# STM.net
KiCad netlist of a schematic drawn in Altium Designer
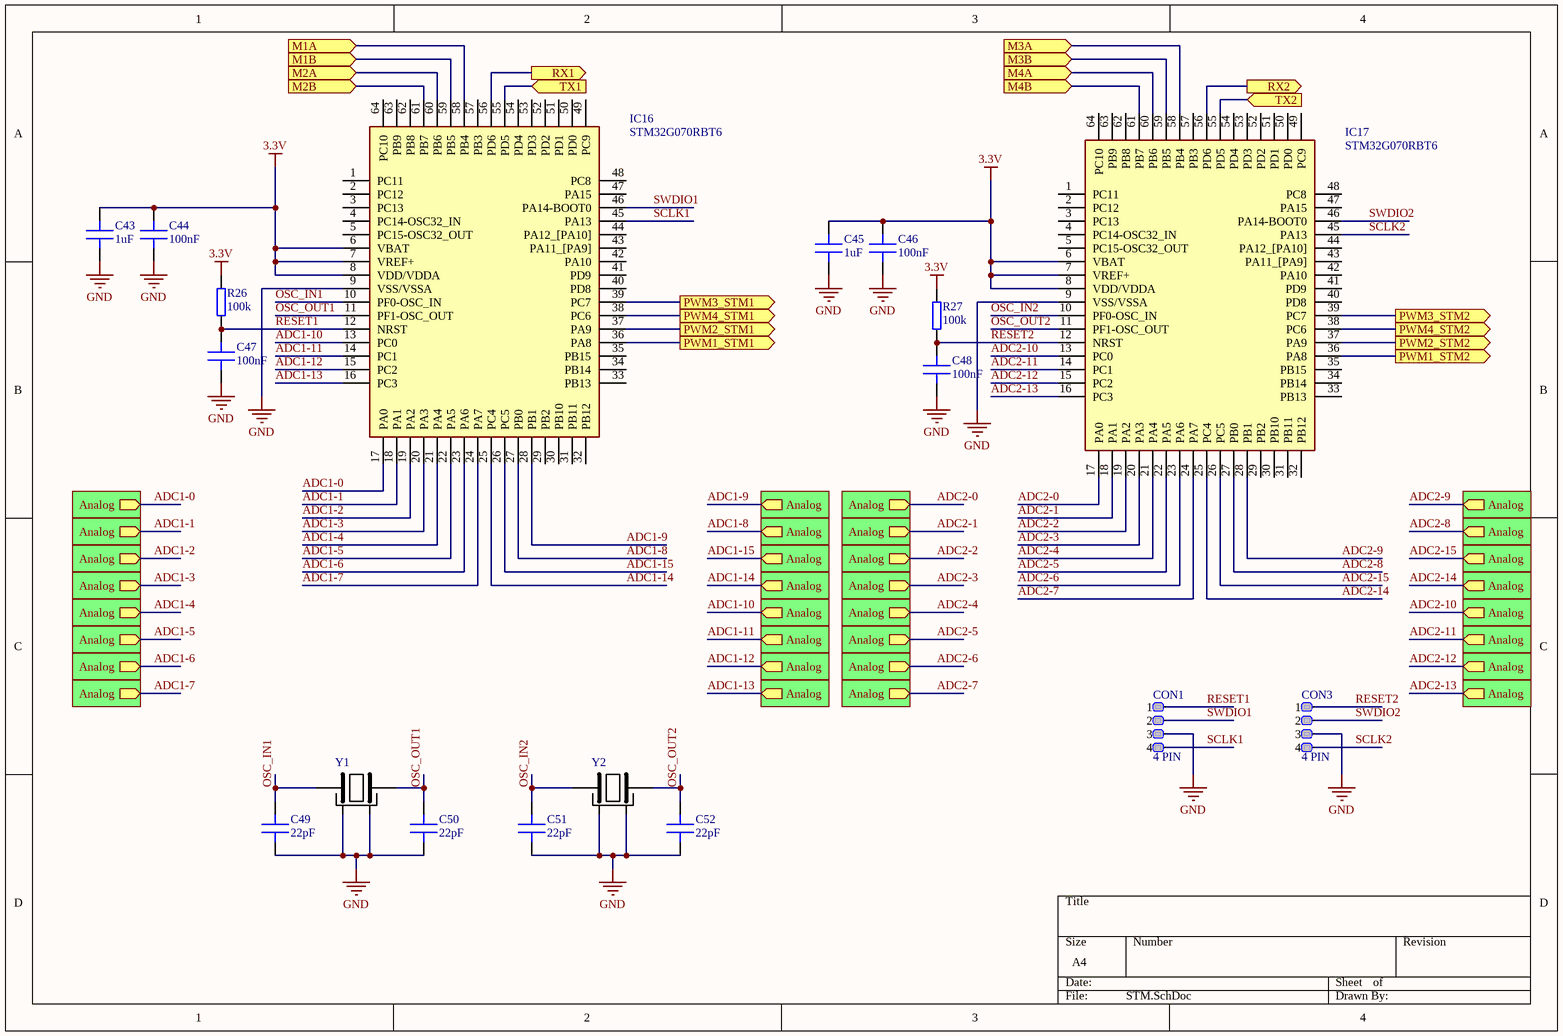
[diagram p0: STM.SchDoc]

(export (version "E")
  (design (tool "Eeschema 10.0.6"))
  (components
    (comp (ref "C43")
      (value "1uF")
      (footprint "C 0402")
      (description "MLCC Capacitor")
      (libsource (lib "Components") (part "Capacitor"))
    )
    (comp (ref "C44")
      (value "100nF")
      (footprint "C 0402")
      (description "MLCC Capacitor")
      (libsource (lib "Components") (part "Capacitor"))
    )
    (comp (ref "C45")
      (value "1uF")
      (footprint "C 0402")
      (description "MLCC Capacitor")
      (libsource (lib "Components") (part "Capacitor"))
    )
    (comp (ref "C46")
      (value "100nF")
      (footprint "C 0402")
      (description "MLCC Capacitor")
      (libsource (lib "Components") (part "Capacitor"))
    )
    (comp (ref "C47")
      (value "100nF")
      (footprint "C 0402")
      (description "MLCC Capacitor")
      (libsource (lib "Components") (part "Capacitor"))
    )
    (comp (ref "C48")
      (value "100nF")
      (footprint "C 0402")
      (description "MLCC Capacitor")
      (libsource (lib "Components") (part "Capacitor"))
    )
    (comp (ref "C49")
      (value "22pF")
      (footprint "C 0402")
      (description "MLCC Capacitor")
      (libsource (lib "Components") (part "Capacitor"))
    )
    (comp (ref "C50")
      (value "22pF")
      (footprint "C 0402")
      (description "MLCC Capacitor")
      (libsource (lib "Components") (part "Capacitor"))
    )
    (comp (ref "C51")
      (value "22pF")
      (footprint "C 0402")
      (description "MLCC Capacitor")
      (libsource (lib "Components") (part "Capacitor"))
    )
    (comp (ref "C52")
      (value "22pF")
      (footprint "C 0402")
      (description "MLCC Capacitor")
      (libsource (lib "Components") (part "Capacitor"))
    )
    (comp (ref "CON1")
      (value "4 PIN")
      (footprint "BM04B-SRSS-TB")
      (libsource (lib "Connectors") (part "4 PIN"))
    )
    (comp (ref "CON3")
      (value "4 PIN")
      (footprint "BM04B-SRSS-TB")
      (libsource (lib "Connectors") (part "4 PIN"))
    )
    (comp (ref "IC16")
      (value "STM32G070RBT6")
      (footprint "SamacSys:QFP50P1200X1200X160-64N")
      (description "Integrated Circuit")
      (fields (field (name "MOUSER PART NUMBER") "511-STM32G070RBT6"))
      (libsource (lib "*") (part "STM32G070RBT6"))
    )
    (comp (ref "IC17")
      (value "STM32G070RBT6")
      (footprint "SamacSys:QFP50P1200X1200X160-64N")
      (description "Integrated Circuit")
      (fields (field (name "MOUSER PART NUMBER") "511-STM32G070RBT6"))
      (libsource (lib "*") (part "STM32G070RBT6"))
    )
    (comp (ref "R26")
      (value "100k")
      (footprint "R 0402")
      (description "General pourpouse resistor")
      (libsource (lib "Components") (part "Resistor"))
    )
    (comp (ref "R27")
      (value "100k")
      (footprint "R 0402")
      (description "General pourpouse resistor")
      (libsource (lib "Components") (part "Resistor"))
    )
    (comp (ref "Y1")
      (value "MCSJK-7U-16.00-12-30-80-B-30")
      (footprint "MCSJK7U1600123080B30")
      (description "Crystal or Oscillator")
      (libsource (lib "SamaSycLibraies") (part "MCSJK-7U-16.00-12-30-80-B-30"))
    )
    (comp (ref "Y2")
      (value "MCSJK-7U-16.00-12-30-80-B-30")
      (footprint "MCSJK7U1600123080B30")
      (description "Crystal or Oscillator")
      (libsource (lib "SamaSycLibraies") (part "MCSJK-7U-16.00-12-30-80-B-30"))
    )
  )
  (nets
    (net (code "1") (name "/ADC1-0") (class "Default")
      (node (ref "IC16") (pin "17") (pinfunction "PA0_17") (pintype "passive"))
    )
    (net (code "2") (name "/ADC1-1") (class "Default")
      (node (ref "IC16") (pin "18") (pinfunction "PA1_18") (pintype "passive"))
    )
    (net (code "3") (name "/ADC1-2") (class "Default")
      (node (ref "IC16") (pin "19") (pinfunction "PA2_19") (pintype "passive"))
    )
    (net (code "4") (name "/ADC1-3") (class "Default")
      (node (ref "IC16") (pin "20") (pinfunction "PA3_20") (pintype "passive"))
    )
    (net (code "5") (name "/ADC1-4") (class "Default")
      (node (ref "IC16") (pin "21") (pinfunction "PA4_21") (pintype "passive"))
    )
    (net (code "6") (name "/ADC1-5") (class "Default")
      (node (ref "IC16") (pin "22") (pinfunction "PA5_22") (pintype "passive"))
    )
    (net (code "7") (name "/ADC1-6") (class "Default")
      (node (ref "IC16") (pin "23") (pinfunction "PA6_23") (pintype "passive"))
    )
    (net (code "8") (name "/ADC1-7") (class "Default")
      (node (ref "IC16") (pin "24") (pinfunction "PA7_24") (pintype "passive"))
    )
    (net (code "9") (name "/ADC1-8") (class "Default")
      (node (ref "IC16") (pin "27") (pinfunction "PB0_27") (pintype "passive"))
    )
    (net (code "10") (name "/ADC1-9") (class "Default")
      (node (ref "IC16") (pin "28") (pinfunction "PB1_28") (pintype "passive"))
    )
    (net (code "11") (name "/ADC1-10") (class "Default")
      (node (ref "IC16") (pin "13") (pinfunction "PC0_13") (pintype "passive"))
    )
    (net (code "12") (name "/ADC1-11") (class "Default")
      (node (ref "IC16") (pin "14") (pinfunction "PC1_14") (pintype "passive"))
    )
    (net (code "13") (name "/ADC1-12") (class "Default")
      (node (ref "IC16") (pin "15") (pinfunction "PC2_15") (pintype "passive"))
    )
    (net (code "14") (name "/ADC1-13") (class "Default")
      (node (ref "IC16") (pin "16") (pinfunction "PC3_16") (pintype "passive"))
    )
    (net (code "15") (name "/ADC1-14") (class "Default")
      (node (ref "IC16") (pin "25") (pinfunction "PC4_25") (pintype "passive"))
    )
    (net (code "16") (name "/ADC1-15") (class "Default")
      (node (ref "IC16") (pin "26") (pinfunction "PC5_26") (pintype "passive"))
    )
    (net (code "17") (name "/ADC2-0") (class "Default")
      (node (ref "IC17") (pin "17") (pinfunction "PA0_17") (pintype "passive"))
    )
    (net (code "18") (name "/ADC2-1") (class "Default")
      (node (ref "IC17") (pin "18") (pinfunction "PA1_18") (pintype "passive"))
    )
    (net (code "19") (name "/ADC2-2") (class "Default")
      (node (ref "IC17") (pin "19") (pinfunction "PA2_19") (pintype "passive"))
    )
    (net (code "20") (name "/ADC2-3") (class "Default")
      (node (ref "IC17") (pin "20") (pinfunction "PA3_20") (pintype "passive"))
    )
    (net (code "21") (name "/ADC2-4") (class "Default")
      (node (ref "IC17") (pin "21") (pinfunction "PA4_21") (pintype "passive"))
    )
    (net (code "22") (name "/ADC2-5") (class "Default")
      (node (ref "IC17") (pin "22") (pinfunction "PA5_22") (pintype "passive"))
    )
    (net (code "23") (name "/ADC2-6") (class "Default")
      (node (ref "IC17") (pin "23") (pinfunction "PA6_23") (pintype "passive"))
    )
    (net (code "24") (name "/ADC2-7") (class "Default")
      (node (ref "IC17") (pin "24") (pinfunction "PA7_24") (pintype "passive"))
    )
    (net (code "25") (name "/ADC2-8") (class "Default")
      (node (ref "IC17") (pin "27") (pinfunction "PB0_27") (pintype "passive"))
    )
    (net (code "26") (name "/ADC2-9") (class "Default")
      (node (ref "IC17") (pin "28") (pinfunction "PB1_28") (pintype "passive"))
    )
    (net (code "27") (name "/ADC2-10") (class "Default")
      (node (ref "IC17") (pin "13") (pinfunction "PC0_13") (pintype "passive"))
    )
    (net (code "28") (name "/ADC2-11") (class "Default")
      (node (ref "IC17") (pin "14") (pinfunction "PC1_14") (pintype "passive"))
    )
    (net (code "29") (name "/ADC2-12") (class "Default")
      (node (ref "IC17") (pin "15") (pinfunction "PC2_15") (pintype "passive"))
    )
    (net (code "30") (name "/ADC2-13") (class "Default")
      (node (ref "IC17") (pin "16") (pinfunction "PC3_16") (pintype "passive"))
    )
    (net (code "31") (name "/ADC2-14") (class "Default")
      (node (ref "IC17") (pin "25") (pinfunction "PC4_25") (pintype "passive"))
    )
    (net (code "32") (name "/ADC2-15") (class "Default")
      (node (ref "IC17") (pin "26") (pinfunction "PC5_26") (pintype "passive"))
    )
    (net (code "33") (name "/M1A") (class "Default")
      (node (ref "IC16") (pin "58") (pinfunction "PB4_58") (pintype "passive"))
    )
    (net (code "34") (name "/M1B") (class "Default")
      (node (ref "IC16") (pin "59") (pinfunction "PB5_59") (pintype "passive"))
    )
    (net (code "35") (name "/M2A") (class "Default")
      (node (ref "IC16") (pin "60") (pinfunction "PB6_60") (pintype "passive"))
    )
    (net (code "36") (name "/M2B") (class "Default")
      (node (ref "IC16") (pin "61") (pinfunction "PB7_61") (pintype "passive"))
    )
    (net (code "37") (name "/M3A") (class "Default")
      (node (ref "IC17") (pin "58") (pinfunction "PB4_58") (pintype "passive"))
    )
    (net (code "38") (name "/M3B") (class "Default")
      (node (ref "IC17") (pin "59") (pinfunction "PB5_59") (pintype "passive"))
    )
    (net (code "39") (name "/M4A") (class "Default")
      (node (ref "IC17") (pin "60") (pinfunction "PB6_60") (pintype "passive"))
    )
    (net (code "40") (name "/M4B") (class "Default")
      (node (ref "IC17") (pin "61") (pinfunction "PB7_61") (pintype "passive"))
    )
    (net (code "41") (name "/OSC_IN1") (class "Default")
      (node (ref "C49") (pin "1") (pinfunction "1_1") (pintype "passive"))
      (node (ref "IC16") (pin "10") (pinfunction "PF0-OSC_IN_10") (pintype "passive"))
      (node (ref "Y1") (pin "1") (pinfunction "CRYSTAL_1_1") (pintype "passive"))
    )
    (net (code "42") (name "/OSC_IN2") (class "Default")
      (node (ref "C51") (pin "1") (pinfunction "1_1") (pintype "passive"))
      (node (ref "IC17") (pin "10") (pinfunction "PF0-OSC_IN_10") (pintype "passive"))
      (node (ref "Y2") (pin "1") (pinfunction "CRYSTAL_1_1") (pintype "passive"))
    )
    (net (code "43") (name "/OSC_OUT1") (class "Default")
      (node (ref "C50") (pin "1") (pinfunction "1_1") (pintype "passive"))
      (node (ref "IC16") (pin "11") (pinfunction "PF1-OSC_OUT_11") (pintype "passive"))
      (node (ref "Y1") (pin "3") (pinfunction "CRYSTAL_2_3") (pintype "passive"))
    )
    (net (code "44") (name "/OSC_OUT2") (class "Default")
      (node (ref "C52") (pin "1") (pinfunction "1_1") (pintype "passive"))
      (node (ref "IC17") (pin "11") (pinfunction "PF1-OSC_OUT_11") (pintype "passive"))
      (node (ref "Y2") (pin "3") (pinfunction "CRYSTAL_2_3") (pintype "passive"))
    )
    (net (code "45") (name "/PWM1_STM1") (class "Default")
      (node (ref "IC16") (pin "36") (pinfunction "PA8_36") (pintype "passive"))
    )
    (net (code "46") (name "/PWM1_STM2") (class "Default")
      (node (ref "IC17") (pin "36") (pinfunction "PA8_36") (pintype "passive"))
    )
    (net (code "47") (name "/PWM2_STM1") (class "Default")
      (node (ref "IC16") (pin "37") (pinfunction "PA9_37") (pintype "passive"))
    )
    (net (code "48") (name "/PWM2_STM2") (class "Default")
      (node (ref "IC17") (pin "37") (pinfunction "PA9_37") (pintype "passive"))
    )
    (net (code "49") (name "/PWM3_STM1") (class "Default")
      (node (ref "IC16") (pin "39") (pinfunction "PC7_39") (pintype "passive"))
    )
    (net (code "50") (name "/PWM3_STM2") (class "Default")
      (node (ref "IC17") (pin "39") (pinfunction "PC7_39") (pintype "passive"))
    )
    (net (code "51") (name "/PWM4_STM1") (class "Default")
      (node (ref "IC16") (pin "38") (pinfunction "PC6_38") (pintype "passive"))
    )
    (net (code "52") (name "/PWM4_STM2") (class "Default")
      (node (ref "IC17") (pin "38") (pinfunction "PC6_38") (pintype "passive"))
    )
    (net (code "53") (name "/RESET1") (class "Default")
      (node (ref "C47") (pin "1") (pinfunction "1_1") (pintype "passive"))
      (node (ref "CON1") (pin "1") (pinfunction "1_1") (pintype "passive"))
      (node (ref "IC16") (pin "12") (pinfunction "NRST_12") (pintype "passive"))
      (node (ref "R26") (pin "1") (pinfunction "1_1") (pintype "passive"))
    )
    (net (code "54") (name "/RESET2") (class "Default")
      (node (ref "C48") (pin "1") (pinfunction "1_1") (pintype "passive"))
      (node (ref "CON3") (pin "1") (pinfunction "1_1") (pintype "passive"))
      (node (ref "IC17") (pin "12") (pinfunction "NRST_12") (pintype "passive"))
      (node (ref "R27") (pin "1") (pinfunction "1_1") (pintype "passive"))
    )
    (net (code "55") (name "/RX1") (class "Default")
      (node (ref "IC16") (pin "56") (pinfunction "PD6_56") (pintype "passive"))
    )
    (net (code "56") (name "/RX2") (class "Default")
      (node (ref "IC17") (pin "56") (pinfunction "PD6_56") (pintype "passive"))
    )
    (net (code "57") (name "/SCLK1") (class "Default")
      (node (ref "CON1") (pin "4") (pinfunction "4_4") (pintype "passive"))
      (node (ref "IC16") (pin "45") (pinfunction "PA13_45") (pintype "passive"))
    )
    (net (code "58") (name "/SCLK2") (class "Default")
      (node (ref "CON3") (pin "4") (pinfunction "4_4") (pintype "passive"))
      (node (ref "IC17") (pin "45") (pinfunction "PA13_45") (pintype "passive"))
    )
    (net (code "59") (name "/SWDIO1") (class "Default")
      (node (ref "CON1") (pin "2") (pinfunction "2_2") (pintype "passive"))
      (node (ref "IC16") (pin "46") (pinfunction "PA14-BOOT0_46") (pintype "passive"))
    )
    (net (code "60") (name "/SWDIO2") (class "Default")
      (node (ref "CON3") (pin "2") (pinfunction "2_2") (pintype "passive"))
      (node (ref "IC17") (pin "46") (pinfunction "PA14-BOOT0_46") (pintype "passive"))
    )
    (net (code "61") (name "/TX1") (class "Default")
      (node (ref "IC16") (pin "55") (pinfunction "PD5_55") (pintype "passive"))
    )
    (net (code "62") (name "/TX2") (class "Default")
      (node (ref "IC17") (pin "55") (pinfunction "PD5_55") (pintype "passive"))
    )
    (net (code "63") (name "3.3V") (class "Default")
      (node (ref "C43") (pin "1") (pinfunction "1_1") (pintype "passive"))
      (node (ref "C44") (pin "1") (pinfunction "1_1") (pintype "passive"))
      (node (ref "C45") (pin "1") (pinfunction "1_1") (pintype "passive"))
      (node (ref "C46") (pin "1") (pinfunction "1_1") (pintype "passive"))
      (node (ref "IC16") (pin "6") (pinfunction "VBAT_6") (pintype "passive"))
      (node (ref "IC16") (pin "7") (pinfunction "VREF+_7") (pintype "passive"))
      (node (ref "IC16") (pin "8") (pinfunction "VDD/VDDA_8") (pintype "passive"))
      (node (ref "IC17") (pin "6") (pinfunction "VBAT_6") (pintype "passive"))
      (node (ref "IC17") (pin "7") (pinfunction "VREF+_7") (pintype "passive"))
      (node (ref "IC17") (pin "8") (pinfunction "VDD/VDDA_8") (pintype "passive"))
      (node (ref "R26") (pin "2") (pinfunction "2_2") (pintype "passive"))
      (node (ref "R27") (pin "2") (pinfunction "2_2") (pintype "passive"))
    )
    (net (code "64") (name "GND") (class "Default")
      (node (ref "C43") (pin "2") (pinfunction "2_2") (pintype "passive"))
      (node (ref "C44") (pin "2") (pinfunction "2_2") (pintype "passive"))
      (node (ref "C45") (pin "2") (pinfunction "2_2") (pintype "passive"))
      (node (ref "C46") (pin "2") (pinfunction "2_2") (pintype "passive"))
      (node (ref "C47") (pin "2") (pinfunction "2_2") (pintype "passive"))
      (node (ref "C48") (pin "2") (pinfunction "2_2") (pintype "passive"))
      (node (ref "C49") (pin "2") (pinfunction "2_2") (pintype "passive"))
      (node (ref "C50") (pin "2") (pinfunction "2_2") (pintype "passive"))
      (node (ref "C51") (pin "2") (pinfunction "2_2") (pintype "passive"))
      (node (ref "C52") (pin "2") (pinfunction "2_2") (pintype "passive"))
      (node (ref "CON1") (pin "3") (pinfunction "3_3") (pintype "passive"))
      (node (ref "CON3") (pin "3") (pinfunction "3_3") (pintype "passive"))
      (node (ref "IC16") (pin "9") (pinfunction "VSS/VSSA_9") (pintype "passive"))
      (node (ref "IC17") (pin "9") (pinfunction "VSS/VSSA_9") (pintype "passive"))
      (node (ref "Y1") (pin "2") (pinfunction "GND_1_2") (pintype "passive"))
      (node (ref "Y1") (pin "4") (pinfunction "GND_2_4") (pintype "passive"))
      (node (ref "Y2") (pin "2") (pinfunction "GND_1_2") (pintype "passive"))
      (node (ref "Y2") (pin "4") (pinfunction "GND_2_4") (pintype "passive"))
    )
    (net (code "65") (name "unconnected-(IC16-PA10-Pad42)") (class "Default")
      (node (ref "IC16") (pin "42") (pinfunction "PA10_42") (pintype "passive"))
    )
    (net (code "66") (name "unconnected-(IC16-PA11_[PA9]-Pad43)") (class "Default")
      (node (ref "IC16") (pin "43") (pinfunction "PA11_[PA9]_43") (pintype "passive"))
    )
    (net (code "67") (name "unconnected-(IC16-PA12_[PA10]-Pad44)") (class "Default")
      (node (ref "IC16") (pin "44") (pinfunction "PA12_[PA10]_44") (pintype "passive"))
    )
    (net (code "68") (name "unconnected-(IC16-PA15-Pad47)") (class "Default")
      (node (ref "IC16") (pin "47") (pinfunction "PA15_47") (pintype "passive"))
    )
    (net (code "69") (name "unconnected-(IC16-PB2-Pad29)") (class "Default")
      (node (ref "IC16") (pin "29") (pinfunction "PB2_29") (pintype "passive"))
    )
    (net (code "70") (name "unconnected-(IC16-PB3-Pad57)") (class "Default")
      (node (ref "IC16") (pin "57") (pinfunction "PB3_57") (pintype "passive"))
    )
    (net (code "71") (name "unconnected-(IC16-PB8-Pad62)") (class "Default")
      (node (ref "IC16") (pin "62") (pinfunction "PB8_62") (pintype "passive"))
    )
    (net (code "72") (name "unconnected-(IC16-PB9-Pad63)") (class "Default")
      (node (ref "IC16") (pin "63") (pinfunction "PB9_63") (pintype "passive"))
    )
    (net (code "73") (name "unconnected-(IC16-PB10-Pad30)") (class "Default")
      (node (ref "IC16") (pin "30") (pinfunction "PB10_30") (pintype "passive"))
    )
    (net (code "74") (name "unconnected-(IC16-PB11-Pad31)") (class "Default")
      (node (ref "IC16") (pin "31") (pinfunction "PB11_31") (pintype "passive"))
    )
    (net (code "75") (name "unconnected-(IC16-PB12-Pad32)") (class "Default")
      (node (ref "IC16") (pin "32") (pinfunction "PB12_32") (pintype "passive"))
    )
    (net (code "76") (name "unconnected-(IC16-PB13-Pad33)") (class "Default")
      (node (ref "IC16") (pin "33") (pinfunction "PB13_33") (pintype "passive"))
    )
    (net (code "77") (name "unconnected-(IC16-PB14-Pad34)") (class "Default")
      (node (ref "IC16") (pin "34") (pinfunction "PB14_34") (pintype "passive"))
    )
    (net (code "78") (name "unconnected-(IC16-PB15-Pad35)") (class "Default")
      (node (ref "IC16") (pin "35") (pinfunction "PB15_35") (pintype "passive"))
    )
    (net (code "79") (name "unconnected-(IC16-PC8-Pad48)") (class "Default")
      (node (ref "IC16") (pin "48") (pinfunction "PC8_48") (pintype "passive"))
    )
    (net (code "80") (name "unconnected-(IC16-PC9-Pad49)") (class "Default")
      (node (ref "IC16") (pin "49") (pinfunction "PC9_49") (pintype "passive"))
    )
    (net (code "81") (name "unconnected-(IC16-PC10-Pad64)") (class "Default")
      (node (ref "IC16") (pin "64") (pinfunction "PC10_64") (pintype "passive"))
    )
    (net (code "82") (name "unconnected-(IC16-PC11-Pad1)") (class "Default")
      (node (ref "IC16") (pin "1") (pinfunction "PC11_1") (pintype "passive"))
    )
    (net (code "83") (name "unconnected-(IC16-PC12-Pad2)") (class "Default")
      (node (ref "IC16") (pin "2") (pinfunction "PC12_2") (pintype "passive"))
    )
    (net (code "84") (name "unconnected-(IC16-PC13-Pad3)") (class "Default")
      (node (ref "IC16") (pin "3") (pinfunction "PC13_3") (pintype "passive"))
    )
    (net (code "85") (name "unconnected-(IC16-PC14-OSC32_IN-Pad4)") (class "Default")
      (node (ref "IC16") (pin "4") (pinfunction "PC14-OSC32_IN_4") (pintype "passive"))
    )
    (net (code "86") (name "unconnected-(IC16-PC15-OSC32_OUT-Pad5)") (class "Default")
      (node (ref "IC16") (pin "5") (pinfunction "PC15-OSC32_OUT_5") (pintype "passive"))
    )
    (net (code "87") (name "unconnected-(IC16-PD0-Pad50)") (class "Default")
      (node (ref "IC16") (pin "50") (pinfunction "PD0_50") (pintype "passive"))
    )
    (net (code "88") (name "unconnected-(IC16-PD1-Pad51)") (class "Default")
      (node (ref "IC16") (pin "51") (pinfunction "PD1_51") (pintype "passive"))
    )
    (net (code "89") (name "unconnected-(IC16-PD2-Pad52)") (class "Default")
      (node (ref "IC16") (pin "52") (pinfunction "PD2_52") (pintype "passive"))
    )
    (net (code "90") (name "unconnected-(IC16-PD3-Pad53)") (class "Default")
      (node (ref "IC16") (pin "53") (pinfunction "PD3_53") (pintype "passive"))
    )
    (net (code "91") (name "unconnected-(IC16-PD4-Pad54)") (class "Default")
      (node (ref "IC16") (pin "54") (pinfunction "PD4_54") (pintype "passive"))
    )
    (net (code "92") (name "unconnected-(IC16-PD8-Pad40)") (class "Default")
      (node (ref "IC16") (pin "40") (pinfunction "PD8_40") (pintype "passive"))
    )
    (net (code "93") (name "unconnected-(IC16-PD9-Pad41)") (class "Default")
      (node (ref "IC16") (pin "41") (pinfunction "PD9_41") (pintype "passive"))
    )
    (net (code "94") (name "unconnected-(IC17-PA10-Pad42)") (class "Default")
      (node (ref "IC17") (pin "42") (pinfunction "PA10_42") (pintype "passive"))
    )
    (net (code "95") (name "unconnected-(IC17-PA11_[PA9]-Pad43)") (class "Default")
      (node (ref "IC17") (pin "43") (pinfunction "PA11_[PA9]_43") (pintype "passive"))
    )
    (net (code "96") (name "unconnected-(IC17-PA12_[PA10]-Pad44)") (class "Default")
      (node (ref "IC17") (pin "44") (pinfunction "PA12_[PA10]_44") (pintype "passive"))
    )
    (net (code "97") (name "unconnected-(IC17-PA15-Pad47)") (class "Default")
      (node (ref "IC17") (pin "47") (pinfunction "PA15_47") (pintype "passive"))
    )
    (net (code "98") (name "unconnected-(IC17-PB2-Pad29)") (class "Default")
      (node (ref "IC17") (pin "29") (pinfunction "PB2_29") (pintype "passive"))
    )
    (net (code "99") (name "unconnected-(IC17-PB3-Pad57)") (class "Default")
      (node (ref "IC17") (pin "57") (pinfunction "PB3_57") (pintype "passive"))
    )
    (net (code "100") (name "unconnected-(IC17-PB8-Pad62)") (class "Default")
      (node (ref "IC17") (pin "62") (pinfunction "PB8_62") (pintype "passive"))
    )
    (net (code "101") (name "unconnected-(IC17-PB9-Pad63)") (class "Default")
      (node (ref "IC17") (pin "63") (pinfunction "PB9_63") (pintype "passive"))
    )
    (net (code "102") (name "unconnected-(IC17-PB10-Pad30)") (class "Default")
      (node (ref "IC17") (pin "30") (pinfunction "PB10_30") (pintype "passive"))
    )
    (net (code "103") (name "unconnected-(IC17-PB11-Pad31)") (class "Default")
      (node (ref "IC17") (pin "31") (pinfunction "PB11_31") (pintype "passive"))
    )
    (net (code "104") (name "unconnected-(IC17-PB12-Pad32)") (class "Default")
      (node (ref "IC17") (pin "32") (pinfunction "PB12_32") (pintype "passive"))
    )
    (net (code "105") (name "unconnected-(IC17-PB13-Pad33)") (class "Default")
      (node (ref "IC17") (pin "33") (pinfunction "PB13_33") (pintype "passive"))
    )
    (net (code "106") (name "unconnected-(IC17-PB14-Pad34)") (class "Default")
      (node (ref "IC17") (pin "34") (pinfunction "PB14_34") (pintype "passive"))
    )
    (net (code "107") (name "unconnected-(IC17-PB15-Pad35)") (class "Default")
      (node (ref "IC17") (pin "35") (pinfunction "PB15_35") (pintype "passive"))
    )
    (net (code "108") (name "unconnected-(IC17-PC8-Pad48)") (class "Default")
      (node (ref "IC17") (pin "48") (pinfunction "PC8_48") (pintype "passive"))
    )
    (net (code "109") (name "unconnected-(IC17-PC9-Pad49)") (class "Default")
      (node (ref "IC17") (pin "49") (pinfunction "PC9_49") (pintype "passive"))
    )
    (net (code "110") (name "unconnected-(IC17-PC10-Pad64)") (class "Default")
      (node (ref "IC17") (pin "64") (pinfunction "PC10_64") (pintype "passive"))
    )
    (net (code "111") (name "unconnected-(IC17-PC11-Pad1)") (class "Default")
      (node (ref "IC17") (pin "1") (pinfunction "PC11_1") (pintype "passive"))
    )
    (net (code "112") (name "unconnected-(IC17-PC12-Pad2)") (class "Default")
      (node (ref "IC17") (pin "2") (pinfunction "PC12_2") (pintype "passive"))
    )
    (net (code "113") (name "unconnected-(IC17-PC13-Pad3)") (class "Default")
      (node (ref "IC17") (pin "3") (pinfunction "PC13_3") (pintype "passive"))
    )
    (net (code "114") (name "unconnected-(IC17-PC14-OSC32_IN-Pad4)") (class "Default")
      (node (ref "IC17") (pin "4") (pinfunction "PC14-OSC32_IN_4") (pintype "passive"))
    )
    (net (code "115") (name "unconnected-(IC17-PC15-OSC32_OUT-Pad5)") (class "Default")
      (node (ref "IC17") (pin "5") (pinfunction "PC15-OSC32_OUT_5") (pintype "passive"))
    )
    (net (code "116") (name "unconnected-(IC17-PD0-Pad50)") (class "Default")
      (node (ref "IC17") (pin "50") (pinfunction "PD0_50") (pintype "passive"))
    )
    (net (code "117") (name "unconnected-(IC17-PD1-Pad51)") (class "Default")
      (node (ref "IC17") (pin "51") (pinfunction "PD1_51") (pintype "passive"))
    )
    (net (code "118") (name "unconnected-(IC17-PD2-Pad52)") (class "Default")
      (node (ref "IC17") (pin "52") (pinfunction "PD2_52") (pintype "passive"))
    )
    (net (code "119") (name "unconnected-(IC17-PD3-Pad53)") (class "Default")
      (node (ref "IC17") (pin "53") (pinfunction "PD3_53") (pintype "passive"))
    )
    (net (code "120") (name "unconnected-(IC17-PD4-Pad54)") (class "Default")
      (node (ref "IC17") (pin "54") (pinfunction "PD4_54") (pintype "passive"))
    )
    (net (code "121") (name "unconnected-(IC17-PD8-Pad40)") (class "Default")
      (node (ref "IC17") (pin "40") (pinfunction "PD8_40") (pintype "passive"))
    )
    (net (code "122") (name "unconnected-(IC17-PD9-Pad41)") (class "Default")
      (node (ref "IC17") (pin "41") (pinfunction "PD9_41") (pintype "passive"))
    )
  )
)
